# polulu_power.net
KiCad netlist of a schematic drawn in Altium Designer
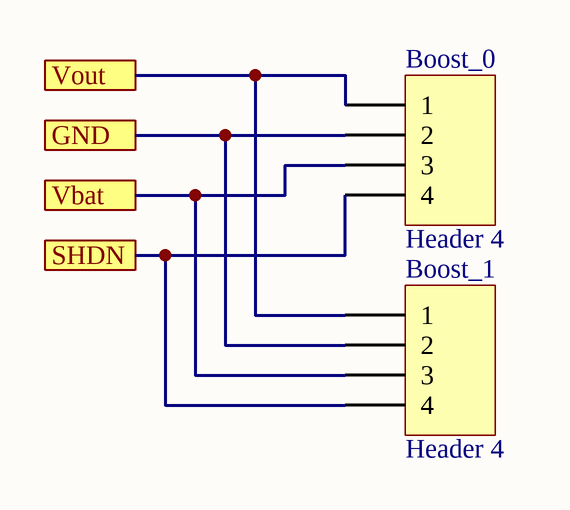
[diagram p0: polulu_power.SchDoc]

(export (version "E")
  (design (tool "Eeschema 10.0.6"))
  (components
    (comp (ref "Boost_0")
      (value "Header 4")
      (footprint "HDR1X4")
      (description "Header, 4-Pin")
      (fields (field (name "PUBLISHER") "Altium Limited"))
      (libsource (lib "Miscellaneous Connectors") (part "Header 4"))
    )
    (comp (ref "Boost_1")
      (value "Header 4")
      (footprint "HDR1X4")
      (description "Header, 4-Pin")
      (fields (field (name "PUBLISHER") "Altium Limited"))
      (libsource (lib "Miscellaneous Connectors") (part "Header 4"))
    )
  )
  (nets
    (net (code "1") (name "/GND") (class "Default")
      (node (ref "Boost_0") (pin "2") (pinfunction "2_2") (pintype "passive"))
      (node (ref "Boost_1") (pin "2") (pinfunction "2_2") (pintype "passive"))
    )
    (net (code "2") (name "/SHDN") (class "Default")
      (node (ref "Boost_0") (pin "4") (pinfunction "4_4") (pintype "passive"))
      (node (ref "Boost_1") (pin "4") (pinfunction "4_4") (pintype "passive"))
    )
    (net (code "3") (name "/Vbat") (class "Default")
      (node (ref "Boost_0") (pin "3") (pinfunction "3_3") (pintype "passive"))
      (node (ref "Boost_1") (pin "3") (pinfunction "3_3") (pintype "passive"))
    )
    (net (code "4") (name "/Vout") (class "Default")
      (node (ref "Boost_0") (pin "1") (pinfunction "1_1") (pintype "passive"))
      (node (ref "Boost_1") (pin "1") (pinfunction "1_1") (pintype "passive"))
    )
  )
)
